# EStop_grn_term.net
KiCad netlist of a schematic drawn in EAGLE
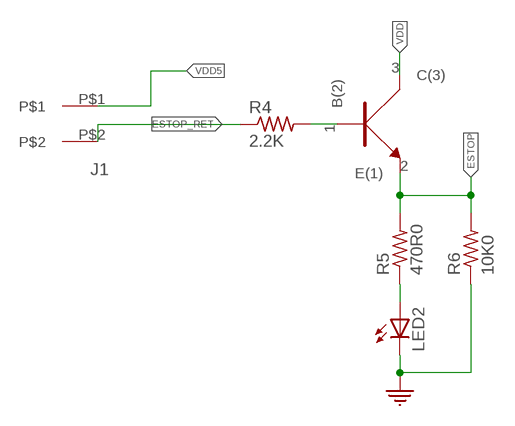
[diagram p0: schematic, sheet 1]

(export (version "E")
  (design (tool "Eeschema 10.0.6"))
  (components
    (comp (ref "J1")
      (value "2-pos")
      (footprint "eagle-import:2_3.81MM_PITCH")
      (fields (field (name "PARTNO") "691322310002"))
      (libsource (lib "eagle-import") (part "3.81MM_1_X_2_RT_ANGLE_PLUG_HEADER"))
    )
    (comp (ref "LED2")
      (value "Green")
      (footprint "eagle-import:0805")
      (fields (field (name "PARTNO") "LG R971-KN-1"))
      (libsource (lib "eagle-import") (part "LED_0805_GREEN"))
    )
    (comp (ref "R4")
      (value "2.2K")
      (footprint "eagle-import:0402")
      (libsource (lib "eagle-import") (part "R_0402"))
    )
    (comp (ref "R5")
      (value "470R0")
      (footprint "eagle-import:0402")
      (fields (field (name "PARTNO") "RMCF0402JT470R"))
      (libsource (lib "eagle-import") (part "R_0402_470R0"))
    )
    (comp (ref "R6")
      (value "10K0")
      (footprint "eagle-import:0402")
      (fields (field (name "PARTNO") "RMCF0402JT10K0"))
      (libsource (lib "eagle-import") (part "R_0402_10K0"))
    )
    (comp (ref "U2")
      (value "NPN")
      (footprint "eagle-import:SOT323")
      (fields (field (name "PARTNO") "BC846BW_NPN"))
      (libsource (lib "eagle-import") (part "BC846BW"))
    )
  )
  (nets
    (net (code "1") (name "ESTOP") (class "Default")
      (node (ref "R5") (pin "P$2") (pinfunction "2_P$2") (pintype "passive"))
      (node (ref "R6") (pin "P$2") (pinfunction "2_P$2") (pintype "passive"))
      (node (ref "U2") (pin "2") (pinfunction "E(1)_2") (pintype "output"))
    )
    (net (code "2") (name "ESTOP_RET") (class "Default")
      (node (ref "J1") (pin "P$2") (pinfunction "P$2_P$2") (pintype "bidirectional"))
      (node (ref "R4") (pin "P$1") (pinfunction "1_P$1") (pintype "passive"))
    )
    (net (code "3") (name "GND") (class "Default")
      (node (ref "LED2") (pin "2") (pinfunction "C_2") (pintype "passive"))
      (node (ref "R6") (pin "P$1") (pinfunction "1_P$1") (pintype "passive"))
    )
    (net (code "4") (name "Net-(LED2-A)") (class "Default")
      (node (ref "LED2") (pin "1") (pinfunction "A_1") (pintype "passive"))
      (node (ref "R5") (pin "P$1") (pinfunction "1_P$1") (pintype "passive"))
    )
    (net (code "5") (name "Net-(R4-2)") (class "Default")
      (node (ref "R4") (pin "P$2") (pinfunction "2_P$2") (pintype "passive"))
      (node (ref "U2") (pin "1") (pinfunction "B(2)_1") (pintype "input"))
    )
    (net (code "6") (name "VDD") (class "Default")
      (node (ref "U2") (pin "3") (pinfunction "C(3)_3") (pintype "input"))
    )
    (net (code "7") (name "VDD5") (class "Default")
      (node (ref "J1") (pin "P$1") (pinfunction "P$1_P$1") (pintype "bidirectional"))
    )
  )
)
